# IO-module-8x_fused_in-wall_35x25.net
KiCad netlist of a schematic drawn in EAGLE
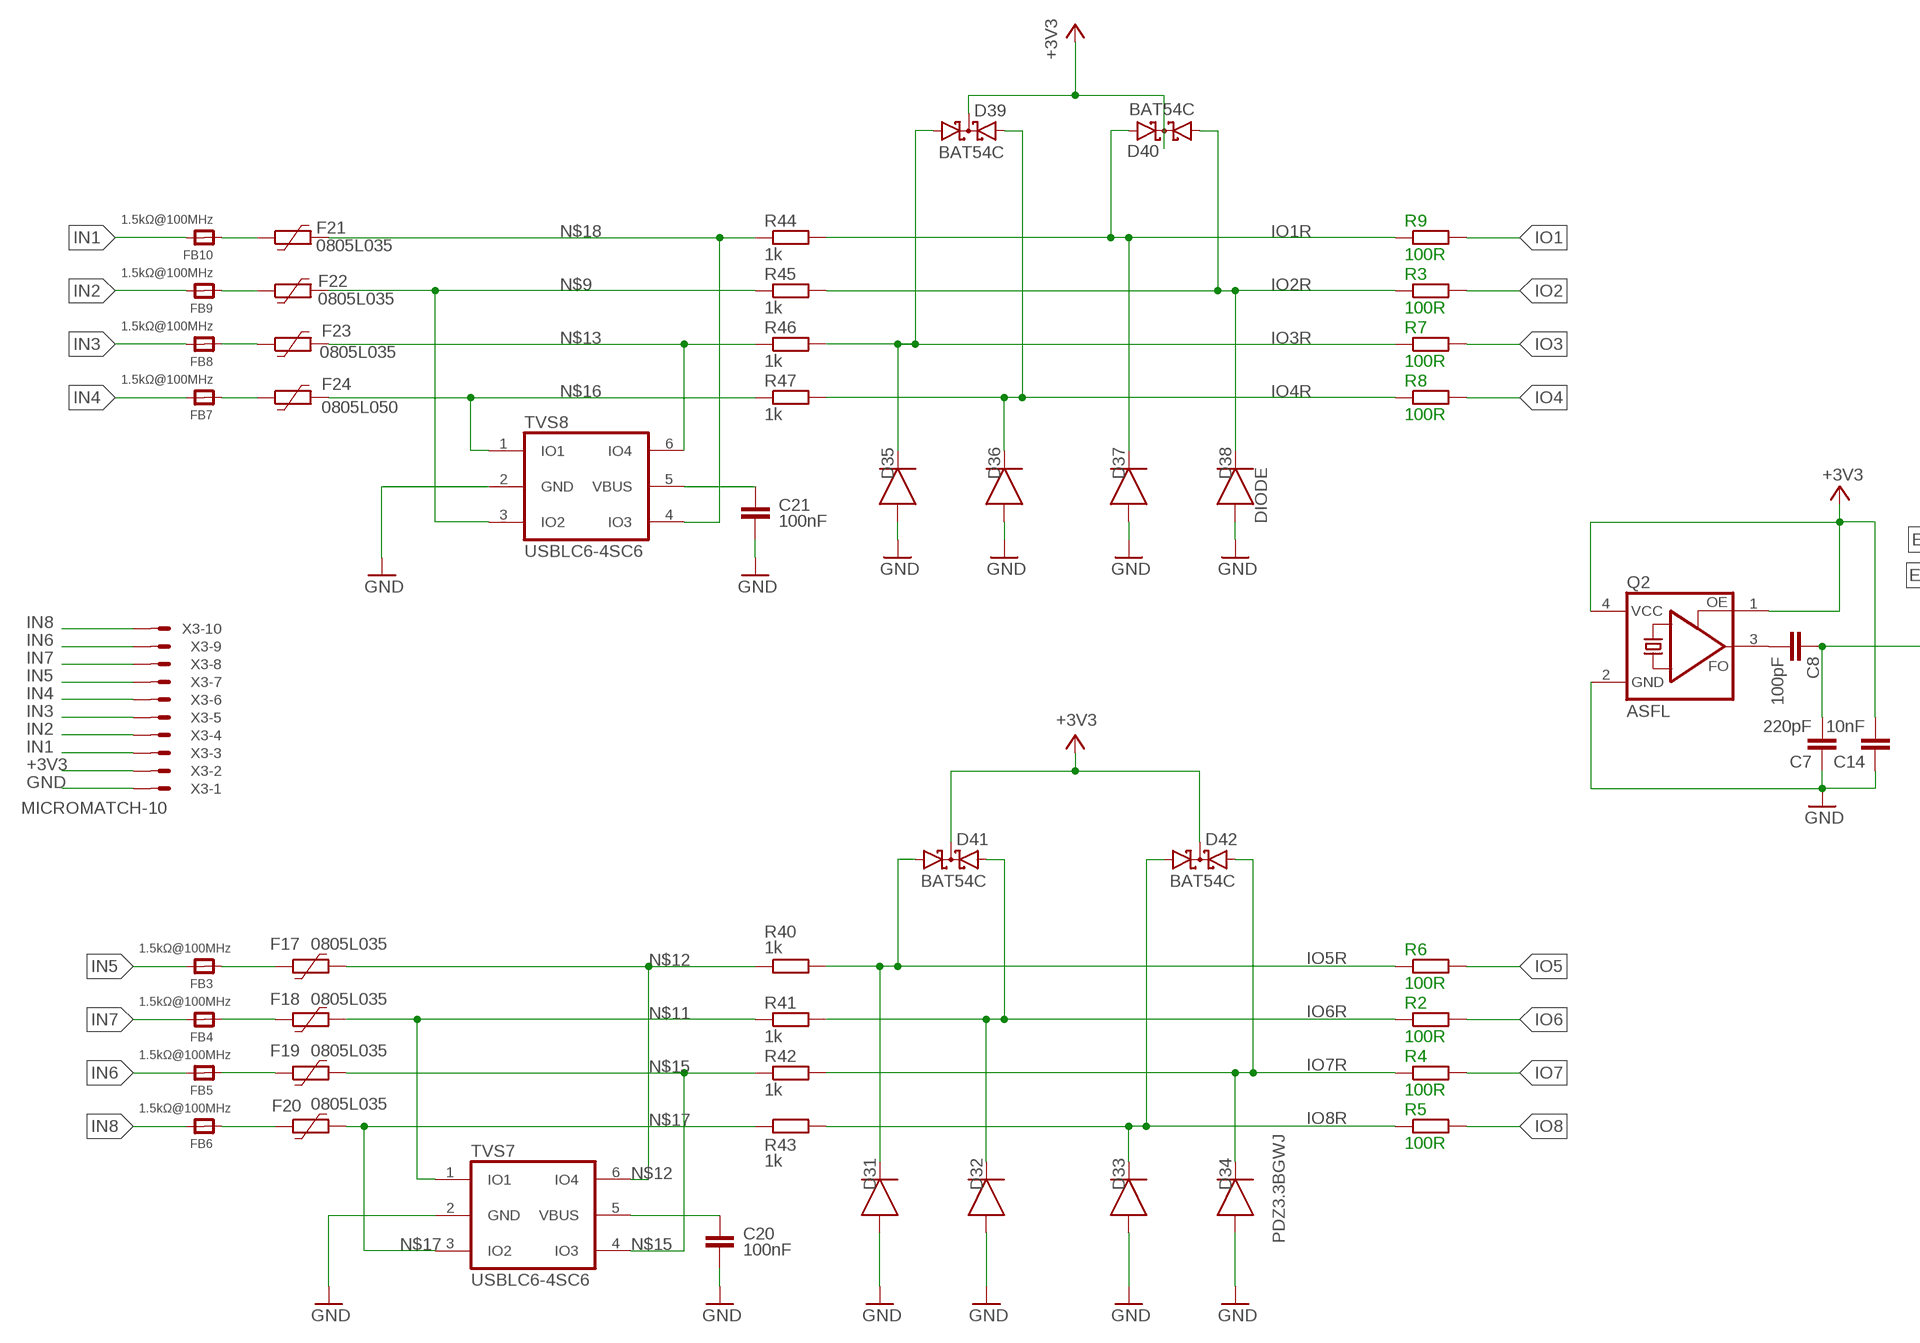
[diagram p0: schematic, sheet 1, part 1 of 2]
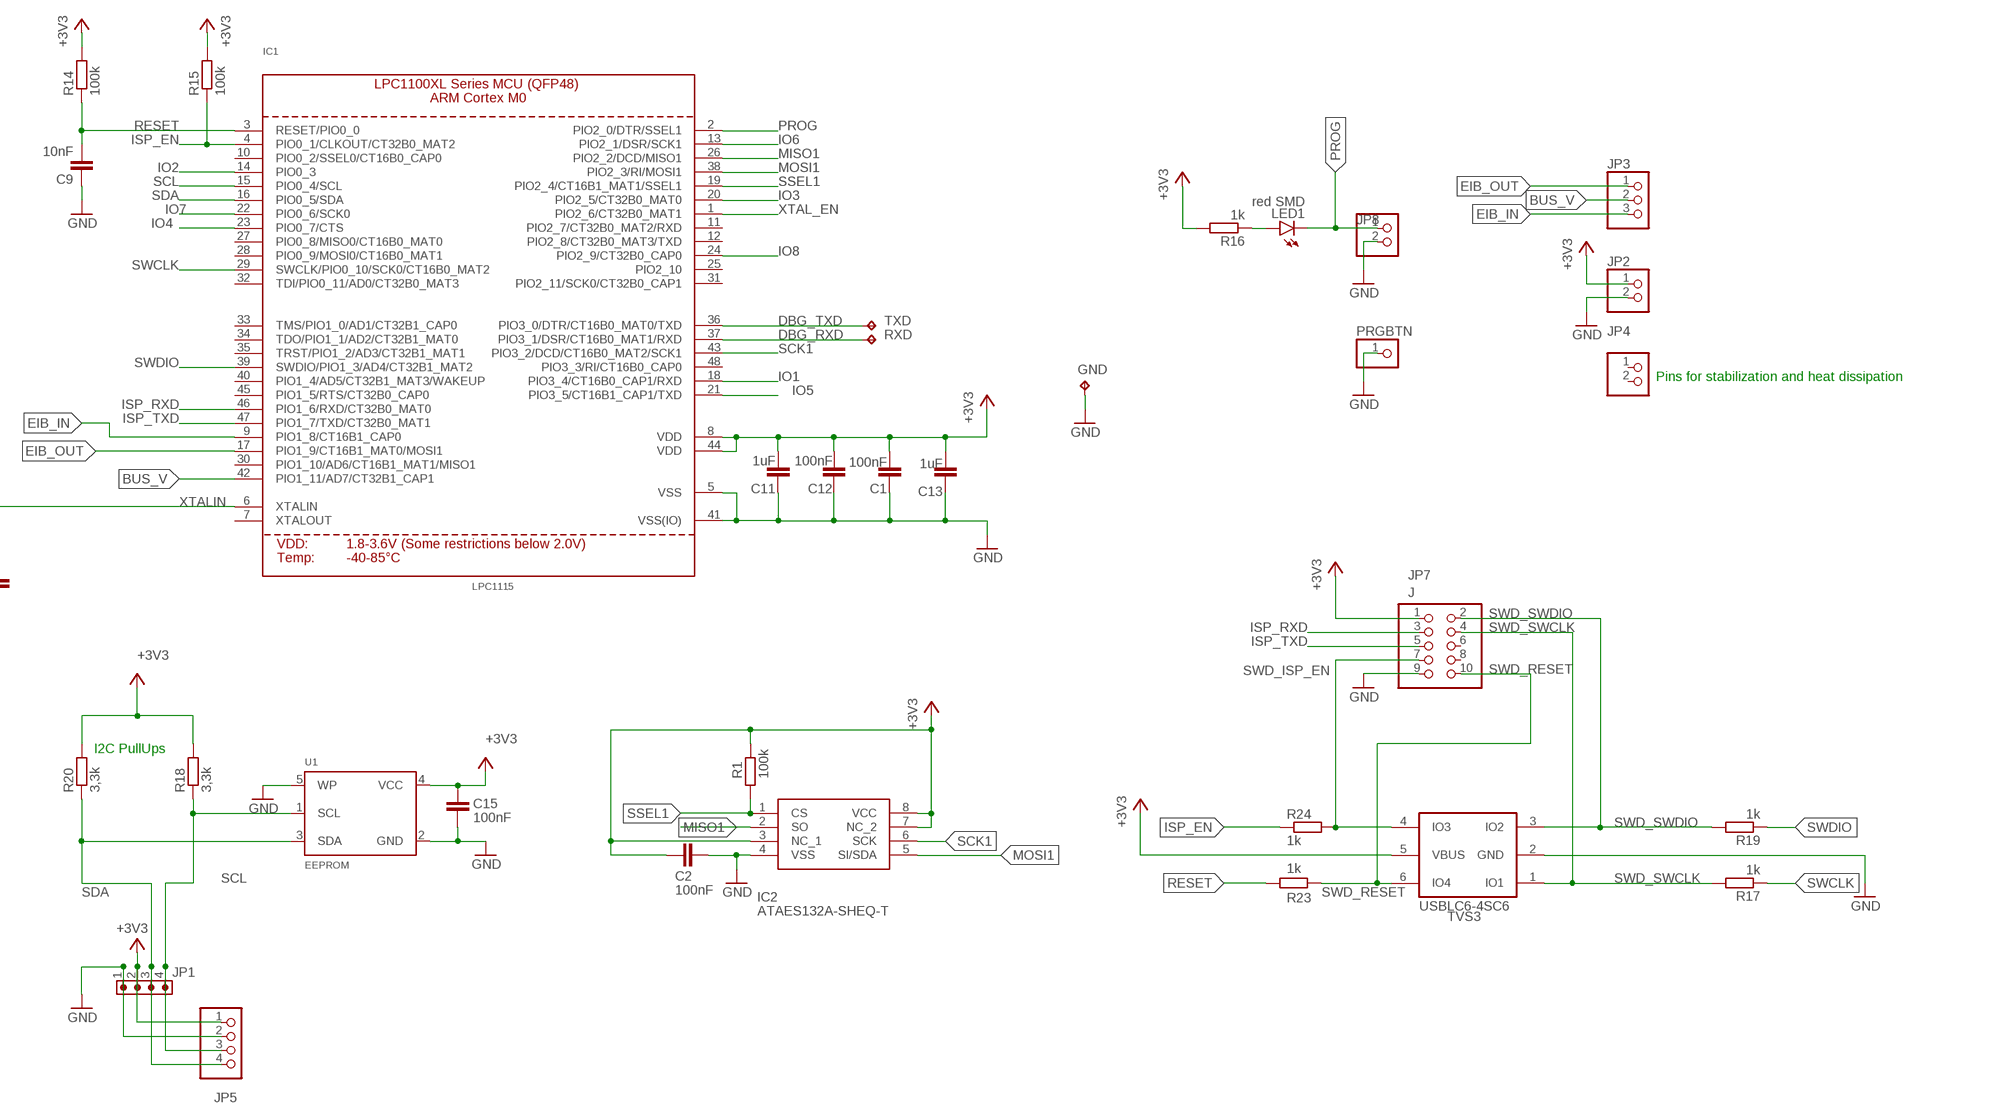
[diagram p1: schematic, sheet 1, part 2 of 2]

(export (version "E")
  (design (tool "Eeschema 10.0.6"))
  (components
    (comp (ref "C1")
      (value "100nF")
      (footprint "eagle-import:C0805")
      (libsource (lib "eagle-import") (part "C-EUC0805"))
    )
    (comp (ref "C2")
      (value "100nF")
      (footprint "eagle-import:C0805")
      (libsource (lib "eagle-import") (part "C-EUC0805"))
    )
    (comp (ref "C7")
      (value "220pF")
      (footprint "eagle-import:C0805")
      (libsource (lib "eagle-import") (part "C-EUC0805"))
    )
    (comp (ref "C8")
      (value "100pF")
      (footprint "eagle-import:C0805")
      (libsource (lib "eagle-import") (part "C-EUC0805"))
    )
    (comp (ref "C9")
      (value "10nF")
      (footprint "eagle-import:C0805")
      (libsource (lib "eagle-import") (part "C-EUC0805"))
    )
    (comp (ref "C11")
      (value "1uF")
      (footprint "eagle-import:C0805")
      (libsource (lib "eagle-import") (part "C-EUC0805"))
    )
    (comp (ref "C12")
      (value "100nF")
      (footprint "eagle-import:C0805")
      (libsource (lib "eagle-import") (part "C-EUC0805"))
    )
    (comp (ref "C13")
      (value "1uF")
      (footprint "eagle-import:C0805")
      (libsource (lib "eagle-import") (part "C-EUC0805"))
    )
    (comp (ref "C14")
      (value "10nF")
      (footprint "eagle-import:C0805")
      (libsource (lib "eagle-import") (part "C-EUC0805"))
    )
    (comp (ref "C15")
      (value "100nF")
      (footprint "eagle-import:C0805")
      (libsource (lib "eagle-import") (part "C-EUC0805"))
    )
    (comp (ref "C20")
      (value "100nF")
      (footprint "eagle-import:C0805")
      (libsource (lib "eagle-import") (part "C-EUC0805"))
    )
    (comp (ref "C21")
      (value "100nF")
      (footprint "eagle-import:C0805")
      (libsource (lib "eagle-import") (part "C-EUC0805"))
    )
    (comp (ref "D31")
      (value "DDZ9684")
      (footprint "eagle-import:SODFL3718X115")
      (libsource (lib "eagle-import") (part "DIODEDO-219-AB(SOD123F)_"))
    )
    (comp (ref "D32")
      (value "DIODE")
      (footprint "eagle-import:SODFL3718X115")
      (libsource (lib "eagle-import") (part "DIODEDO-219-AB(SOD123F)_"))
    )
    (comp (ref "D33")
      (value "DIODE")
      (footprint "eagle-import:SODFL3718X115")
      (libsource (lib "eagle-import") (part "DIODEDO-219-AB(SOD123F)_"))
    )
    (comp (ref "D34")
      (value "PDZ3.3BGWJ")
      (footprint "eagle-import:SODFL3718X115")
      (libsource (lib "eagle-import") (part "DIODEDO-219-AB(SOD123F)_"))
    )
    (comp (ref "D35")
      (value "DIODE")
      (footprint "eagle-import:SODFL3718X115")
      (libsource (lib "eagle-import") (part "DIODEDO-219-AB(SOD123F)_"))
    )
    (comp (ref "D36")
      (value "DIODE")
      (footprint "eagle-import:SODFL3718X115")
      (libsource (lib "eagle-import") (part "DIODEDO-219-AB(SOD123F)_"))
    )
    (comp (ref "D37")
      (value "DIODE")
      (footprint "eagle-import:SODFL3718X115")
      (libsource (lib "eagle-import") (part "DIODEDO-219-AB(SOD123F)_"))
    )
    (comp (ref "D38")
      (value "DIODE")
      (footprint "eagle-import:SODFL3718X115")
      (libsource (lib "eagle-import") (part "DIODEDO-219-AB(SOD123F)_"))
    )
    (comp (ref "D39")
      (value "BAT54C")
      (footprint "eagle-import:SOT23")
      (libsource (lib "eagle-import") (part "BAT54C"))
    )
    (comp (ref "D40")
      (value "BAT54C")
      (footprint "eagle-import:SOT23")
      (libsource (lib "eagle-import") (part "BAT54C"))
    )
    (comp (ref "D41")
      (value "BAT54C")
      (footprint "eagle-import:SOT23")
      (libsource (lib "eagle-import") (part "BAT54C"))
    )
    (comp (ref "D42")
      (value "BAT54C")
      (footprint "eagle-import:SOT23")
      (libsource (lib "eagle-import") (part "BAT54C"))
    )
    (comp (ref "F17")
      (value "0805L035")
      (footprint "eagle-import:0805L")
      (fields (field (name "MF") "Littelfuse"))
      (libsource (lib "eagle-import") (part "?0805L035"))
    )
    (comp (ref "F18")
      (value "0805L035")
      (footprint "eagle-import:0805L")
      (fields (field (name "MF") "Littelfuse"))
      (libsource (lib "eagle-import") (part "?0805L035"))
    )
    (comp (ref "F19")
      (value "0805L035")
      (footprint "eagle-import:0805L")
      (fields (field (name "MF") "Littelfuse"))
      (libsource (lib "eagle-import") (part "?0805L035"))
    )
    (comp (ref "F20")
      (value "0805L035")
      (footprint "eagle-import:0805L")
      (fields (field (name "MF") "Littelfuse"))
      (libsource (lib "eagle-import") (part "?0805L035"))
    )
    (comp (ref "F21")
      (value "0805L035")
      (footprint "eagle-import:0805L")
      (fields (field (name "MF") "Littelfuse"))
      (libsource (lib "eagle-import") (part "?0805L035"))
    )
    (comp (ref "F22")
      (value "0805L035")
      (footprint "eagle-import:0805L")
      (fields (field (name "MF") "Littelfuse"))
      (libsource (lib "eagle-import") (part "?0805L035"))
    )
    (comp (ref "F23")
      (value "0805L035")
      (footprint "eagle-import:0805L")
      (fields (field (name "MF") "Littelfuse"))
      (libsource (lib "eagle-import") (part "?0805L035"))
    )
    (comp (ref "F24")
      (value "0805L050")
      (footprint "eagle-import:0805L")
      (fields (field (name "MF") "Littelfuse"))
      (libsource (lib "eagle-import") (part "?0805L050"))
    )
    (comp (ref "FB3")
      (value "1.5kΩ@100MHz")
      (footprint "eagle-import:0805")
      (libsource (lib "eagle-import") (part "FERRITE0805"))
    )
    (comp (ref "FB4")
      (value "1.5kΩ@100MHz")
      (footprint "eagle-import:0805")
      (libsource (lib "eagle-import") (part "FERRITE0805"))
    )
    (comp (ref "FB5")
      (value "1.5kΩ@100MHz")
      (footprint "eagle-import:0805")
      (libsource (lib "eagle-import") (part "FERRITE0805"))
    )
    (comp (ref "FB6")
      (value "1.5kΩ@100MHz")
      (footprint "eagle-import:0805")
      (libsource (lib "eagle-import") (part "FERRITE0805"))
    )
    (comp (ref "FB7")
      (value "1.5kΩ@100MHz")
      (footprint "eagle-import:0805")
      (libsource (lib "eagle-import") (part "FERRITE0805"))
    )
    (comp (ref "FB8")
      (value "1.5kΩ@100MHz")
      (footprint "eagle-import:0805")
      (libsource (lib "eagle-import") (part "FERRITE0805"))
    )
    (comp (ref "FB9")
      (value "1.5kΩ@100MHz")
      (footprint "eagle-import:0805")
      (libsource (lib "eagle-import") (part "FERRITE0805"))
    )
    (comp (ref "FB10")
      (value "1.5kΩ@100MHz")
      (footprint "eagle-import:0805")
      (libsource (lib "eagle-import") (part "FERRITE0805"))
    )
    (comp (ref "GND")
      (value "TPTP11SQ")
      (footprint "eagle-import:TP11SQ")
      (libsource (lib "eagle-import") (part "TPTP11SQ"))
    )
    (comp (ref "IC1")
      (value "LPC1115")
      (footprint "eagle-import:LQFP48")
      (libsource (lib "eagle-import") (part "LPC1113/4/5_QFP48_XLSERIES"))
    )
    (comp (ref "IC2")
      (value "ATAES132A-SHEQ-T")
      (footprint "eagle-import:SOIC127P600X175-8N")
      (fields (field (name "MOUSER_PART_NUMBER") "556-ATAES132A-SHEQ-T"))
      (libsource (lib "eagle-import") (part "ATAES132A-SHEQ-T"))
    )
    (comp (ref "JP1")
      (value "62000411622")
      (footprint "eagle-import:62000411622")
      (libsource (lib "eagle-import") (part "62000411622"))
    )
    (comp (ref "JP2")
      (value "PINHD-1X2")
      (footprint "eagle-import:1X02")
      (libsource (lib "eagle-import") (part "PINHD-1X2"))
    )
    (comp (ref "JP3")
      (value "PINHD-1X3")
      (footprint "eagle-import:1X03")
      (libsource (lib "eagle-import") (part "PINHD-1X3"))
    )
    (comp (ref "JP4")
      (value "PINHD-1X2")
      (footprint "eagle-import:1X02")
      (libsource (lib "eagle-import") (part "PINHD-1X2"))
    )
    (comp (ref "JP5")
      (value "PINHD-1X4")
      (footprint "eagle-import:1X04")
      (libsource (lib "eagle-import") (part "PINHD-1X4"))
    )
    (comp (ref "JP7")
      (value "J")
      (footprint "eagle-import:2X05M")
      (libsource (lib "eagle-import") (part "PINHD-2X05_2.00"))
    )
    (comp (ref "JP8")
      (value "PINHD-1X2")
      (footprint "eagle-import:1X02")
      (libsource (lib "eagle-import") (part "PINHD-1X2"))
    )
    (comp (ref "LED1")
      (value "red SMD")
      (footprint "eagle-import:CHIPLED_1206")
      (libsource (lib "eagle-import") (part "LEDCHIPLED_1206"))
    )
    (comp (ref "PRGBTN")
      (value "PINHD-1X1")
      (footprint "eagle-import:1X01")
      (libsource (lib "eagle-import") (part "PINHD-1X1"))
    )
    (comp (ref "Q2")
      (value "ASFL")
      (footprint "eagle-import:ASF")
      (fields (field (name "MPN") "ASFLM1-50.000MHZ-C-T"))
      (libsource (lib "eagle-import") (part "ASFL"))
    )
    (comp (ref "R1")
      (value "100k")
      (footprint "eagle-import:R0805")
      (libsource (lib "eagle-import") (part "R-EU_R0805"))
    )
    (comp (ref "R2")
      (value "100R")
      (footprint "eagle-import:R0805")
      (libsource (lib "eagle-import") (part "R-EU_R0805"))
    )
    (comp (ref "R3")
      (value "100R")
      (footprint "eagle-import:R0805")
      (libsource (lib "eagle-import") (part "R-EU_R0805"))
    )
    (comp (ref "R4")
      (value "100R")
      (footprint "eagle-import:R0805")
      (libsource (lib "eagle-import") (part "R-EU_R0805"))
    )
    (comp (ref "R5")
      (value "100R")
      (footprint "eagle-import:R0805")
      (libsource (lib "eagle-import") (part "R-EU_R0805"))
    )
    (comp (ref "R6")
      (value "100R")
      (footprint "eagle-import:R0805")
      (libsource (lib "eagle-import") (part "R-EU_R0805"))
    )
    (comp (ref "R7")
      (value "100R")
      (footprint "eagle-import:R0805")
      (libsource (lib "eagle-import") (part "R-EU_R0805"))
    )
    (comp (ref "R8")
      (value "100R")
      (footprint "eagle-import:R0805")
      (libsource (lib "eagle-import") (part "R-EU_R0805"))
    )
    (comp (ref "R9")
      (value "100R")
      (footprint "eagle-import:R0805")
      (libsource (lib "eagle-import") (part "R-EU_R0805"))
    )
    (comp (ref "R14")
      (value "100k")
      (footprint "eagle-import:R0805")
      (libsource (lib "eagle-import") (part "R-EU_R0805"))
    )
    (comp (ref "R15")
      (value "100k")
      (footprint "eagle-import:R0805")
      (libsource (lib "eagle-import") (part "R-EU_R0805"))
    )
    (comp (ref "R16")
      (value "1k")
      (footprint "eagle-import:R0805")
      (libsource (lib "eagle-import") (part "R-EU_R0805"))
    )
    (comp (ref "R17")
      (value "1k")
      (footprint "eagle-import:R0805")
      (libsource (lib "eagle-import") (part "R-EU_R0805"))
    )
    (comp (ref "R18")
      (value "3,3k")
      (footprint "eagle-import:R0805")
      (libsource (lib "eagle-import") (part "R-EU_R0805"))
    )
    (comp (ref "R19")
      (value "1k")
      (footprint "eagle-import:R0805")
      (libsource (lib "eagle-import") (part "R-EU_R0805"))
    )
    (comp (ref "R20")
      (value "3,3k")
      (footprint "eagle-import:R0805")
      (libsource (lib "eagle-import") (part "R-EU_R0805"))
    )
    (comp (ref "R23")
      (value "1k")
      (footprint "eagle-import:R0805")
      (libsource (lib "eagle-import") (part "R-EU_R0805"))
    )
    (comp (ref "R24")
      (value "1k")
      (footprint "eagle-import:R0805")
      (libsource (lib "eagle-import") (part "R-EU_R0805"))
    )
    (comp (ref "R40")
      (value "1k")
      (footprint "eagle-import:R0805")
      (libsource (lib "eagle-import") (part "R-EU_R0805"))
    )
    (comp (ref "R41")
      (value "1k")
      (footprint "eagle-import:R0805")
      (libsource (lib "eagle-import") (part "R-EU_R0805"))
    )
    (comp (ref "R42")
      (value "1k")
      (footprint "eagle-import:R0805")
      (libsource (lib "eagle-import") (part "R-EU_R0805"))
    )
    (comp (ref "R43")
      (value "1k")
      (footprint "eagle-import:R0805")
      (libsource (lib "eagle-import") (part "R-EU_R0805"))
    )
    (comp (ref "R44")
      (value "1k")
      (footprint "eagle-import:R0805")
      (libsource (lib "eagle-import") (part "R-EU_R0805"))
    )
    (comp (ref "R45")
      (value "1k")
      (footprint "eagle-import:R0805")
      (libsource (lib "eagle-import") (part "R-EU_R0805"))
    )
    (comp (ref "R46")
      (value "1k")
      (footprint "eagle-import:R0805")
      (libsource (lib "eagle-import") (part "R-EU_R0805"))
    )
    (comp (ref "R47")
      (value "1k")
      (footprint "eagle-import:R0805")
      (libsource (lib "eagle-import") (part "R-EU_R0805"))
    )
    (comp (ref "RXD")
      (value "TPTP12R")
      (footprint "eagle-import:TP12R")
      (libsource (lib "eagle-import") (part "TPTP12R"))
    )
    (comp (ref "TVS3")
      (value "USBLC6-4SC6")
      (footprint "eagle-import:SOT-23-6L")
      (libsource (lib "eagle-import") (part "USBLC6-4SC6"))
    )
    (comp (ref "TVS7")
      (value "USBLC6-4SC6")
      (footprint "eagle-import:SOT-23-6L")
      (libsource (lib "eagle-import") (part "USBLC6-4SC6"))
    )
    (comp (ref "TVS8")
      (value "USBLC6-4SC6")
      (footprint "eagle-import:SOT-23-6L")
      (libsource (lib "eagle-import") (part "USBLC6-4SC6"))
    )
    (comp (ref "TXD")
      (value "TPTP12SQ")
      (footprint "eagle-import:TP12SQ")
      (libsource (lib "eagle-import") (part "TPTP12SQ"))
    )
    (comp (ref "U1")
      (value "EEPROM")
      (footprint "eagle-import:SOT23-5")
      (libsource (lib "eagle-import") (part "EEPROM_I2C_MCP24AA32"))
    )
    (comp (ref "X3")
      (value "MICROMATCH-10")
      (footprint "eagle-import:MICROMATCH-10")
      (fields (field (name "MF") "FARNELL") (field (name "MPN") "8-215464-0"))
      (libsource (lib "eagle-import") (part "MICROMATCH-10"))
    )
  )
  (nets
    (net (code "1") (name "+3V3") (class "Default")
      (node (ref "C1") (pin "2") (pinfunction "2_2") (pintype "passive"))
      (node (ref "C11") (pin "2") (pinfunction "2_2") (pintype "passive"))
      (node (ref "C12") (pin "2") (pinfunction "2_2") (pintype "passive"))
      (node (ref "C13") (pin "2") (pinfunction "2_2") (pintype "passive"))
      (node (ref "C14") (pin "2") (pinfunction "2_2") (pintype "passive"))
      (node (ref "C15") (pin "1") (pinfunction "1_1") (pintype "passive"))
      (node (ref "C2") (pin "1") (pinfunction "1_1") (pintype "passive"))
      (node (ref "D39") (pin "3") (pinfunction "CC_3") (pintype "passive"))
      (node (ref "D40") (pin "3") (pinfunction "CC_3") (pintype "passive"))
      (node (ref "D41") (pin "3") (pinfunction "CC_3") (pintype "passive"))
      (node (ref "D42") (pin "3") (pinfunction "CC_3") (pintype "passive"))
      (node (ref "IC1") (pin "44") (pinfunction "VDD_44") (pintype "power_in"))
      (node (ref "IC1") (pin "8") (pinfunction "VDD_8") (pintype "power_in"))
      (node (ref "IC2") (pin "3") (pinfunction "NC_1_3") (pintype "bidirectional"))
      (node (ref "IC2") (pin "7") (pinfunction "NC_2_7") (pintype "bidirectional"))
      (node (ref "IC2") (pin "8") (pinfunction "VCC_8") (pintype "bidirectional"))
      (node (ref "JP1") (pin "2") (pinfunction "2_2") (pintype "passive"))
      (node (ref "JP2") (pin "1") (pinfunction "1_1") (pintype "passive"))
      (node (ref "JP5") (pin "1") (pinfunction "1_1") (pintype "passive"))
      (node (ref "JP7") (pin "1") (pinfunction "1_1") (pintype "passive"))
      (node (ref "Q2") (pin "1") (pinfunction "OE_1") (pintype "input"))
      (node (ref "Q2") (pin "4") (pinfunction "VCC_4") (pintype "power_in"))
      (node (ref "R1") (pin "2") (pinfunction "2_2") (pintype "passive"))
      (node (ref "R14") (pin "2") (pinfunction "2_2") (pintype "passive"))
      (node (ref "R15") (pin "2") (pinfunction "2_2") (pintype "passive"))
      (node (ref "R16") (pin "2") (pinfunction "2_2") (pintype "passive"))
      (node (ref "R18") (pin "2") (pinfunction "2_2") (pintype "passive"))
      (node (ref "R20") (pin "2") (pinfunction "2_2") (pintype "passive"))
      (node (ref "TVS3") (pin "5") (pinfunction "VBUS_5") (pintype "bidirectional"))
      (node (ref "U1") (pin "4") (pinfunction "VCC_4") (pintype "bidirectional"))
      (node (ref "X3") (pin "2") (pinfunction "S_2") (pintype "passive"))
    )
    (net (code "2") (name "/DBG_RXD") (class "Default")
      (node (ref "IC1") (pin "37") (pinfunction "PIO3_1/DSR/CT16B0_MAT1/RXD_37") (pintype "bidirectional"))
      (node (ref "RXD") (pin "TP") (pinfunction "TP_TP") (pintype "input"))
    )
    (net (code "3") (name "/DBG_TXD") (class "Default")
      (node (ref "IC1") (pin "36") (pinfunction "PIO3_0/DTR/CT16B0_MAT0/TXD_36") (pintype "bidirectional"))
      (node (ref "TXD") (pin "TP") (pinfunction "TP_TP") (pintype "input"))
    )
    (net (code "4") (name "/IO1R") (class "Default")
      (node (ref "D37") (pin "1") (pinfunction "C_1") (pintype "passive"))
      (node (ref "D40") (pin "2") (pinfunction "A2_2") (pintype "passive"))
      (node (ref "R44") (pin "2") (pinfunction "2_2") (pintype "passive"))
      (node (ref "R9") (pin "1") (pinfunction "1_1") (pintype "passive"))
    )
    (net (code "5") (name "/IO2R") (class "Default")
      (node (ref "D38") (pin "1") (pinfunction "C_1") (pintype "passive"))
      (node (ref "D40") (pin "1") (pinfunction "A1_1") (pintype "passive"))
      (node (ref "R3") (pin "1") (pinfunction "1_1") (pintype "passive"))
      (node (ref "R45") (pin "2") (pinfunction "2_2") (pintype "passive"))
    )
    (net (code "6") (name "/IO3R") (class "Default")
      (node (ref "D35") (pin "1") (pinfunction "C_1") (pintype "passive"))
      (node (ref "D39") (pin "1") (pinfunction "A1_1") (pintype "passive"))
      (node (ref "R46") (pin "2") (pinfunction "2_2") (pintype "passive"))
      (node (ref "R7") (pin "1") (pinfunction "1_1") (pintype "passive"))
    )
    (net (code "7") (name "/IO4R") (class "Default")
      (node (ref "D36") (pin "1") (pinfunction "C_1") (pintype "passive"))
      (node (ref "D39") (pin "2") (pinfunction "A2_2") (pintype "passive"))
      (node (ref "R47") (pin "2") (pinfunction "2_2") (pintype "passive"))
      (node (ref "R8") (pin "1") (pinfunction "1_1") (pintype "passive"))
    )
    (net (code "8") (name "/IO5R") (class "Default")
      (node (ref "D31") (pin "1") (pinfunction "C_1") (pintype "passive"))
      (node (ref "D41") (pin "1") (pinfunction "A1_1") (pintype "passive"))
      (node (ref "R40") (pin "2") (pinfunction "2_2") (pintype "passive"))
      (node (ref "R6") (pin "1") (pinfunction "1_1") (pintype "passive"))
    )
    (net (code "9") (name "/IO6R") (class "Default")
      (node (ref "D32") (pin "1") (pinfunction "C_1") (pintype "passive"))
      (node (ref "D41") (pin "2") (pinfunction "A2_2") (pintype "passive"))
      (node (ref "R2") (pin "1") (pinfunction "1_1") (pintype "passive"))
      (node (ref "R41") (pin "2") (pinfunction "2_2") (pintype "passive"))
    )
    (net (code "10") (name "/IO7R") (class "Default")
      (node (ref "D34") (pin "1") (pinfunction "C_1") (pintype "passive"))
      (node (ref "D42") (pin "2") (pinfunction "A2_2") (pintype "passive"))
      (node (ref "R4") (pin "1") (pinfunction "1_1") (pintype "passive"))
      (node (ref "R42") (pin "2") (pinfunction "2_2") (pintype "passive"))
    )
    (net (code "11") (name "/IO8R") (class "Default")
      (node (ref "D33") (pin "1") (pinfunction "C_1") (pintype "passive"))
      (node (ref "D42") (pin "1") (pinfunction "A1_1") (pintype "passive"))
      (node (ref "R43") (pin "2") (pinfunction "2_2") (pintype "passive"))
      (node (ref "R5") (pin "1") (pinfunction "1_1") (pintype "passive"))
    )
    (net (code "12") (name "/ISP_RXD") (class "Default")
      (node (ref "IC1") (pin "46") (pinfunction "PIO1_6/RXD/CT32B0_MAT0_46") (pintype "bidirectional"))
      (node (ref "JP7") (pin "3") (pinfunction "3_3") (pintype "passive"))
    )
    (net (code "13") (name "/ISP_TXD") (class "Default")
      (node (ref "IC1") (pin "47") (pinfunction "PIO1_7/TXD/CT32B0_MAT1_47") (pintype "bidirectional"))
      (node (ref "JP7") (pin "5") (pinfunction "5_5") (pintype "passive"))
    )
    (net (code "14") (name "/N$9") (class "Default")
      (node (ref "F22") (pin "2") (pinfunction "2_2") (pintype "passive"))
      (node (ref "R45") (pin "1") (pinfunction "1_1") (pintype "passive"))
      (node (ref "TVS8") (pin "3") (pinfunction "IO2_3") (pintype "bidirectional"))
    )
    (net (code "15") (name "/N$11") (class "Default")
      (node (ref "F18") (pin "2") (pinfunction "2_2") (pintype "passive"))
      (node (ref "R41") (pin "1") (pinfunction "1_1") (pintype "passive"))
      (node (ref "TVS7") (pin "1") (pinfunction "IO1_1") (pintype "bidirectional"))
    )
    (net (code "16") (name "/N$12") (class "Default")
      (node (ref "F17") (pin "2") (pinfunction "2_2") (pintype "passive"))
      (node (ref "R40") (pin "1") (pinfunction "1_1") (pintype "passive"))
      (node (ref "TVS7") (pin "6") (pinfunction "IO4_6") (pintype "bidirectional"))
    )
    (net (code "17") (name "/N$13") (class "Default")
      (node (ref "F23") (pin "2") (pinfunction "2_2") (pintype "passive"))
      (node (ref "R46") (pin "1") (pinfunction "1_1") (pintype "passive"))
      (node (ref "TVS8") (pin "6") (pinfunction "IO4_6") (pintype "bidirectional"))
    )
    (net (code "18") (name "/N$15") (class "Default")
      (node (ref "F19") (pin "2") (pinfunction "2_2") (pintype "passive"))
      (node (ref "R42") (pin "1") (pinfunction "1_1") (pintype "passive"))
      (node (ref "TVS7") (pin "4") (pinfunction "IO3_4") (pintype "bidirectional"))
    )
    (net (code "19") (name "/N$16") (class "Default")
      (node (ref "F24") (pin "2") (pinfunction "2_2") (pintype "passive"))
      (node (ref "R47") (pin "1") (pinfunction "1_1") (pintype "passive"))
      (node (ref "TVS8") (pin "1") (pinfunction "IO1_1") (pintype "bidirectional"))
    )
    (net (code "20") (name "/N$17") (class "Default")
      (node (ref "F20") (pin "2") (pinfunction "2_2") (pintype "passive"))
      (node (ref "R43") (pin "1") (pinfunction "1_1") (pintype "passive"))
      (node (ref "TVS7") (pin "3") (pinfunction "IO2_3") (pintype "bidirectional"))
    )
    (net (code "21") (name "/N$18") (class "Default")
      (node (ref "F21") (pin "2") (pinfunction "2_2") (pintype "passive"))
      (node (ref "R44") (pin "1") (pinfunction "1_1") (pintype "passive"))
      (node (ref "TVS8") (pin "4") (pinfunction "IO3_4") (pintype "bidirectional"))
    )
    (net (code "22") (name "/SCL") (class "Default")
      (node (ref "IC1") (pin "15") (pinfunction "PIO0_4/SCL_15") (pintype "bidirectional"))
      (node (ref "JP1") (pin "4") (pinfunction "4_4") (pintype "passive"))
      (node (ref "JP5") (pin "3") (pinfunction "3_3") (pintype "passive"))
      (node (ref "R18") (pin "1") (pinfunction "1_1") (pintype "passive"))
      (node (ref "U1") (pin "1") (pinfunction "SCL_1") (pintype "bidirectional"))
    )
    (net (code "23") (name "/SDA") (class "Default")
      (node (ref "IC1") (pin "16") (pinfunction "PIO0_5/SDA_16") (pintype "bidirectional"))
      (node (ref "JP1") (pin "3") (pinfunction "3_3") (pintype "passive"))
      (node (ref "JP5") (pin "4") (pinfunction "4_4") (pintype "passive"))
      (node (ref "R20") (pin "1") (pinfunction "1_1") (pintype "passive"))
      (node (ref "U1") (pin "3") (pinfunction "SDA_3") (pintype "bidirectional"))
    )
    (net (code "24") (name "/SWD_ISP_EN") (class "Default")
      (node (ref "JP7") (pin "7") (pinfunction "7_7") (pintype "passive"))
      (node (ref "R24") (pin "2") (pinfunction "2_2") (pintype "passive"))
      (node (ref "TVS3") (pin "4") (pinfunction "IO3_4") (pintype "bidirectional"))
    )
    (net (code "25") (name "/SWD_RESET") (class "Default")
      (node (ref "JP7") (pin "10") (pinfunction "10_10") (pintype "passive"))
      (node (ref "R23") (pin "1") (pinfunction "1_1") (pintype "passive"))
      (node (ref "TVS3") (pin "6") (pinfunction "IO4_6") (pintype "bidirectional"))
    )
    (net (code "26") (name "/SWD_SWCLK") (class "Default")
      (node (ref "JP7") (pin "4") (pinfunction "4_4") (pintype "passive"))
      (node (ref "R17") (pin "2") (pinfunction "2_2") (pintype "passive"))
      (node (ref "TVS3") (pin "1") (pinfunction "IO1_1") (pintype "bidirectional"))
    )
    (net (code "27") (name "/SWD_SWDIO") (class "Default")
      (node (ref "JP7") (pin "2") (pinfunction "2_2") (pintype "passive"))
      (node (ref "R19") (pin "2") (pinfunction "2_2") (pintype "passive"))
      (node (ref "TVS3") (pin "3") (pinfunction "IO2_3") (pintype "bidirectional"))
    )
    (net (code "28") (name "/XTALIN") (class "Default")
      (node (ref "C7") (pin "2") (pinfunction "2_2") (pintype "passive"))
      (node (ref "C8") (pin "1") (pinfunction "1_1") (pintype "passive"))
      (node (ref "IC1") (pin "6") (pinfunction "XTALIN_6") (pintype "input"))
    )
    (net (code "29") (name "/XTAL_EN") (class "Default")
      (node (ref "IC1") (pin "1") (pinfunction "PIO2_6/CT32B0_MAT1_1") (pintype "bidirectional"))
    )
    (net (code "30") (name "BUS_V") (class "Default")
      (node (ref "IC1") (pin "42") (pinfunction "PIO1_11/AD7/CT32B1_CAP1_42") (pintype "bidirectional"))
      (node (ref "JP3") (pin "2") (pinfunction "2_2") (pintype "passive"))
    )
    (net (code "31") (name "EIB_IN") (class "Default")
      (node (ref "IC1") (pin "9") (pinfunction "PIO1_8/CT16B1_CAP0_9") (pintype "bidirectional"))
      (node (ref "JP3") (pin "3") (pinfunction "3_3") (pintype "passive"))
    )
    (net (code "32") (name "EIB_OUT") (class "Default")
      (node (ref "IC1") (pin "17") (pinfunction "PIO1_9/CT16B1_MAT0/MOSI1_17") (pintype "bidirectional"))
      (node (ref "JP3") (pin "1") (pinfunction "1_1") (pintype "passive"))
    )
    (net (code "33") (name "GND") (class "Default")
      (node (ref "C1") (pin "1") (pinfunction "1_1") (pintype "passive"))
      (node (ref "C11") (pin "1") (pinfunction "1_1") (pintype "passive"))
      (node (ref "C12") (pin "1") (pinfunction "1_1") (pintype "passive"))
      (node (ref "C13") (pin "1") (pinfunction "1_1") (pintype "passive"))
      (node (ref "C14") (pin "1") (pinfunction "1_1") (pintype "passive"))
      (node (ref "C15") (pin "2") (pinfunction "2_2") (pintype "passive"))
      (node (ref "C2") (pin "2") (pinfunction "2_2") (pintype "passive"))
      (node (ref "C20") (pin "1") (pinfunction "1_1") (pintype "passive"))
      (node (ref "C21") (pin "1") (pinfunction "1_1") (pintype "passive"))
      (node (ref "C7") (pin "1") (pinfunction "1_1") (pintype "passive"))
      (node (ref "C9") (pin "1") (pinfunction "1_1") (pintype "passive"))
      (node (ref "D31") (pin "2") (pinfunction "A_2") (pintype "passive"))
      (node (ref "D32") (pin "2") (pinfunction "A_2") (pintype "passive"))
      (node (ref "D33") (pin "2") (pinfunction "A_2") (pintype "passive"))
      (node (ref "D34") (pin "2") (pinfunction "A_2") (pintype "passive"))
      (node (ref "D35") (pin "2") (pinfunction "A_2") (pintype "passive"))
      (node (ref "D36") (pin "2") (pinfunction "A_2") (pintype "passive"))
      (node (ref "D37") (pin "2") (pinfunction "A_2") (pintype "passive"))
      (node (ref "D38") (pin "2") (pinfunction "A_2") (pintype "passive"))
      (node (ref "GND") (pin "TP") (pinfunction "TP_TP") (pintype "input"))
      (node (ref "IC1") (pin "41") (pinfunction "VSS(IO)_41") (pintype "power_in"))
      (node (ref "IC1") (pin "5") (pinfunction "VSS_5") (pintype "power_in"))
      (node (ref "IC2") (pin "4") (pinfunction "VSS_4") (pintype "bidirectional"))
      (node (ref "JP1") (pin "1") (pinfunction "1_1") (pintype "passive"))
      (node (ref "JP2") (pin "2") (pinfunction "2_2") (pintype "passive"))
      (node (ref "JP5") (pin "2") (pinfunction "2_2") (pintype "passive"))
      (node (ref "JP7") (pin "9") (pinfunction "9_9") (pintype "passive"))
      (node (ref "JP8") (pin "2") (pinfunction "2_2") (pintype "passive"))
      (node (ref "PRGBTN") (pin "1") (pinfunction "1_1") (pintype "passive"))
      (node (ref "Q2") (pin "2") (pinfunction "GND_2") (pintype "power_in"))
      (node (ref "TVS3") (pin "2") (pinfunction "GND_2") (pintype "bidirectional"))
      (node (ref "TVS7") (pin "2") (pinfunction "GND_2") (pintype "bidirectional"))
      (node (ref "TVS8") (pin "2") (pinfunction "GND_2") (pintype "bidirectional"))
      (node (ref "U1") (pin "2") (pinfunction "GND_2") (pintype "bidirectional"))
      (node (ref "U1") (pin "5") (pinfunction "WP_5") (pintype "bidirectional"))
      (node (ref "X3") (pin "1") (pinfunction "S_1") (pintype "passive"))
    )
    (net (code "34") (name "IN1") (class "Default")
      (node (ref "FB10") (pin "2") (pinfunction "P$2_2") (pintype "passive"))
      (node (ref "X3") (pin "3") (pinfunction "S_3") (pintype "passive"))
    )
    (net (code "35") (name "IN2") (class "Default")
      (node (ref "FB9") (pin "2") (pinfunction "P$2_2") (pintype "passive"))
      (node (ref "X3") (pin "4") (pinfunction "S_4") (pintype "passive"))
    )
    (net (code "36") (name "IN3") (class "Default")
      (node (ref "FB8") (pin "2") (pinfunction "P$2_2") (pintype "passive"))
      (node (ref "X3") (pin "5") (pinfunction "S_5") (pintype "passive"))
    )
    (net (code "37") (name "IN4") (class "Default")
      (node (ref "FB7") (pin "2") (pinfunction "P$2_2") (pintype "passive"))
      (node (ref "X3") (pin "6") (pinfunction "S_6") (pintype "passive"))
    )
    (net (code "38") (name "IN5") (class "Default")
      (node (ref "FB3") (pin "2") (pinfunction "P$2_2") (pintype "passive"))
      (node (ref "X3") (pin "7") (pinfunction "S_7") (pintype "passive"))
    )
    (net (code "39") (name "IN6") (class "Default")
      (node (ref "FB5") (pin "2") (pinfunction "P$2_2") (pintype "passive"))
      (node (ref "X3") (pin "9") (pinfunction "S_9") (pintype "passive"))
    )
    (net (code "40") (name "IN7") (class "Default")
      (node (ref "FB4") (pin "2") (pinfunction "P$2_2") (pintype "passive"))
      (node (ref "X3") (pin "8") (pinfunction "S_8") (pintype "passive"))
    )
    (net (code "41") (name "IN8") (class "Default")
      (node (ref "FB6") (pin "2") (pinfunction "P$2_2") (pintype "passive"))
      (node (ref "X3") (pin "10") (pinfunction "S_10") (pintype "passive"))
    )
    (net (code "42") (name "IO1") (class "Default")
      (node (ref "IC1") (pin "18") (pinfunction "PIO3_4/CT16B0_CAP1/RXD_18") (pintype "bidirectional"))
      (node (ref "R9") (pin "2") (pinfunction "2_2") (pintype "passive"))
    )
    (net (code "43") (name "IO2") (class "Default")
      (node (ref "IC1") (pin "14") (pinfunction "PIO0_3_14") (pintype "bidirectional"))
      (node (ref "R3") (pin "2") (pinfunction "2_2") (pintype "passive"))
    )
    (net (code "44") (name "IO3") (class "Default")
      (node (ref "IC1") (pin "20") (pinfunction "PIO2_5/CT32B0_MAT0_20") (pintype "bidirectional"))
      (node (ref "R7") (pin "2") (pinfunction "2_2") (pintype "passive"))
    )
    (net (code "45") (name "IO4") (class "Default")
      (node (ref "IC1") (pin "23") (pinfunction "PIO0_7/CTS_23") (pintype "bidirectional"))
      (node (ref "R8") (pin "2") (pinfunction "2_2") (pintype "passive"))
    )
    (net (code "46") (name "IO5") (class "Default")
      (node (ref "IC1") (pin "21") (pinfunction "PIO3_5/CT16B1_CAP1/TXD_21") (pintype "bidirectional"))
      (node (ref "R6") (pin "2") (pinfunction "2_2") (pintype "passive"))
    )
    (net (code "47") (name "IO6") (class "Default")
      (node (ref "IC1") (pin "13") (pinfunction "PIO2_1/DSR/SCK1_13") (pintype "bidirectional"))
      (node (ref "R2") (pin "2") (pinfunction "2_2") (pintype "passive"))
    )
    (net (code "48") (name "IO7") (class "Default")
      (node (ref "IC1") (pin "22") (pinfunction "PIO0_6/SCK0_22") (pintype "bidirectional"))
      (node (ref "R4") (pin "2") (pinfunction "2_2") (pintype "passive"))
    )
    (net (code "49") (name "IO8") (class "Default")
      (node (ref "IC1") (pin "24") (pinfunction "PIO2_9/CT32B0_CAP0_24") (pintype "bidirectional"))
      (node (ref "R5") (pin "2") (pinfunction "2_2") (pintype "passive"))
    )
    (net (code "50") (name "ISP_EN") (class "Default")
      (node (ref "IC1") (pin "4") (pinfunction "PIO0_1/CLKOUT/CT32B0_MAT2_4") (pintype "bidirectional"))
      (node (ref "R15") (pin "1") (pinfunction "1_1") (pintype "passive"))
      (node (ref "R24") (pin "1") (pinfunction "1_1") (pintype "passive"))
    )
    (net (code "51") (name "MISO1") (class "Default")
      (node (ref "IC1") (pin "26") (pinfunction "PIO2_2/DCD/MISO1_26") (pintype "bidirectional"))
      (node (ref "IC2") (pin "2") (pinfunction "SO_2") (pintype "bidirectional"))
    )
    (net (code "52") (name "MOSI1") (class "Default")
      (node (ref "IC1") (pin "38") (pinfunction "PIO2_3/RI/MOSI1_38") (pintype "bidirectional"))
      (node (ref "IC2") (pin "5") (pinfunction "SI/SDA_5") (pintype "bidirectional"))
    )
    (net (code "53") (name "Net-(FB3-P$1)") (class "Default")
      (node (ref "F17") (pin "1") (pinfunction "1_1") (pintype "passive"))
      (node (ref "FB3") (pin "1") (pinfunction "P$1_1") (pintype "passive"))
    )
    (net (code "54") (name "Net-(FB4-P$1)") (class "Default")
      (node (ref "F18") (pin "1") (pinfunction "1_1") (pintype "passive"))
      (node (ref "FB4") (pin "1") (pinfunction "P$1_1") (pintype "passive"))
    )
    (net (code "55") (name "Net-(FB5-P$1)") (class "Default")
      (node (ref "F19") (pin "1") (pinfunction "1_1") (pintype "passive"))
      (node (ref "FB5") (pin "1") (pinfunction "P$1_1") (pintype "passive"))
    )
    (net (code "56") (name "Net-(FB6-P$1)") (class "Default")
      (node (ref "F20") (pin "1") (pinfunction "1_1") (pintype "passive"))
      (node (ref "FB6") (pin "1") (pinfunction "P$1_1") (pintype "passive"))
    )
    (net (code "57") (name "Net-(FB7-P$1)") (class "Default")
      (node (ref "F24") (pin "1") (pinfunction "1_1") (pintype "passive"))
      (node (ref "FB7") (pin "1") (pinfunction "P$1_1") (pintype "passive"))
    )
    (net (code "58") (name "Net-(FB8-P$1)") (class "Default")
      (node (ref "F23") (pin "1") (pinfunction "1_1") (pintype "passive"))
      (node (ref "FB8") (pin "1") (pinfunction "P$1_1") (pintype "passive"))
    )
    (net (code "59") (name "Net-(FB9-P$1)") (class "Default")
      (node (ref "F22") (pin "1") (pinfunction "1_1") (pintype "passive"))
      (node (ref "FB9") (pin "1") (pinfunction "P$1_1") (pintype "passive"))
    )
    (net (code "60") (name "Net-(FB10-P$1)") (class "Default")
      (node (ref "F21") (pin "1") (pinfunction "1_1") (pintype "passive"))
      (node (ref "FB10") (pin "1") (pinfunction "P$1_1") (pintype "passive"))
    )
    (net (code "61") (name "Net-(LED1-PadA)") (class "Default")
      (node (ref "LED1") (pin "A") (pinfunction "A_A") (pintype "passive"))
      (node (ref "R16") (pin "1") (pinfunction "1_1") (pintype "passive"))
    )
    (net (code "62") (name "Net-(Q2-FO)") (class "Default")
      (node (ref "C8") (pin "2") (pinfunction "2_2") (pintype "passive"))
      (node (ref "Q2") (pin "3") (pinfunction "FO_3") (pintype "output"))
    )
    (net (code "63") (name "Net-(TVS7-VBUS)") (class "Default")
      (node (ref "C20") (pin "2") (pinfunction "2_2") (pintype "passive"))
      (node (ref "TVS7") (pin "5") (pinfunction "VBUS_5") (pintype "bidirectional"))
    )
    (net (code "64") (name "Net-(TVS8-VBUS)") (class "Default")
      (node (ref "C21") (pin "2") (pinfunction "2_2") (pintype "passive"))
      (node (ref "TVS8") (pin "5") (pinfunction "VBUS_5") (pintype "bidirectional"))
    )
    (net (code "65") (name "PROG") (class "Default")
      (node (ref "IC1") (pin "2") (pinfunction "PIO2_0/DTR/SSEL1_2") (pintype "bidirectional"))
      (node (ref "JP8") (pin "1") (pinfunction "1_1") (pintype "passive"))
      (node (ref "LED1") (pin "C") (pinfunction "C_C") (pintype "passive"))
    )
    (net (code "66") (name "RESET") (class "Default")
      (node (ref "C9") (pin "2") (pinfunction "2_2") (pintype "passive"))
      (node (ref "IC1") (pin "3") (pinfunction "RESET/PIO0_0_3") (pintype "bidirectional"))
      (node (ref "R14") (pin "1") (pinfunction "1_1") (pintype "passive"))
      (node (ref "R23") (pin "2") (pinfunction "2_2") (pintype "passive"))
    )
    (net (code "67") (name "SCK1") (class "Default")
      (node (ref "IC1") (pin "43") (pinfunction "PIO3_2/DCD/CT16B0_MAT2/SCK1_43") (pintype "bidirectional"))
      (node (ref "IC2") (pin "6") (pinfunction "SCK_6") (pintype "bidirectional"))
    )
    (net (code "68") (name "SSEL1") (class "Default")
      (node (ref "IC1") (pin "19") (pinfunction "PIO2_4/CT16B1_MAT1/SSEL1_19") (pintype "bidirectional"))
      (node (ref "IC2") (pin "1") (pinfunction "CS_1") (pintype "bidirectional"))
      (node (ref "R1") (pin "1") (pinfunction "1_1") (pintype "passive"))
    )
    (net (code "69") (name "SWCLK") (class "Default")
      (node (ref "IC1") (pin "29") (pinfunction "SWCLK/PIO0_10/SCK0/CT16B0_MAT2_29") (pintype "bidirectional"))
      (node (ref "R17") (pin "1") (pinfunction "1_1") (pintype "passive"))
    )
    (net (code "70") (name "SWDIO") (class "Default")
      (node (ref "IC1") (pin "39") (pinfunction "SWDIO/PIO1_3/AD4/CT32B1_MAT2_39") (pintype "bidirectional"))
      (node (ref "R19") (pin "1") (pinfunction "1_1") (pintype "passive"))
    )
    (net (code "71") (name "unconnected-(IC1-PIO0_2{slash}SSEL0{slash}CT16B0_CAP0-Pad10)") (class "Default")
      (node (ref "IC1") (pin "10") (pinfunction "PIO0_2/SSEL0/CT16B0_CAP0_10") (pintype "bidirectional"))
    )
    (net (code "72") (name "unconnected-(IC1-PIO0_8{slash}MISO0{slash}CT16B0_MAT0-Pad27)") (class "Default")
      (node (ref "IC1") (pin "27") (pinfunction "PIO0_8/MISO0/CT16B0_MAT0_27") (pintype "bidirectional"))
    )
    (net (code "73") (name "unconnected-(IC1-PIO0_9{slash}MOSI0{slash}CT16B0_MAT1-Pad28)") (class "Default")
      (node (ref "IC1") (pin "28") (pinfunction "PIO0_9/MOSI0/CT16B0_MAT1_28") (pintype "bidirectional"))
    )
    (net (code "74") (name "unconnected-(IC1-PIO1_4{slash}AD5{slash}CT32B1_MAT3{slash}WAKEUP-Pad40)") (class "Default")
      (node (ref "IC1") (pin "40") (pinfunction "PIO1_4/AD5/CT32B1_MAT3/WAKEUP_40") (pintype "bidirectional"))
    )
    (net (code "75") (name "unconnected-(IC1-PIO1_5{slash}RTS{slash}CT32B0_CAP0-Pad45)") (class "Default")
      (node (ref "IC1") (pin "45") (pinfunction "PIO1_5/RTS/CT32B0_CAP0_45") (pintype "bidirectional"))
    )
    (net (code "76") (name "unconnected-(IC1-PIO1_10{slash}AD6{slash}CT16B1_MAT1{slash}MISO1-Pad30)") (class "Default")
      (node (ref "IC1") (pin "30") (pinfunction "PIO1_10/AD6/CT16B1_MAT1/MISO1_30") (pintype "bidirectional"))
    )
    (net (code "77") (name "unconnected-(IC1-PIO2_7{slash}CT32B0_MAT2{slash}RXD-Pad11)") (class "Default")
      (node (ref "IC1") (pin "11") (pinfunction "PIO2_7/CT32B0_MAT2/RXD_11") (pintype "bidirectional"))
    )
    (net (code "78") (name "unconnected-(IC1-PIO2_8{slash}CT32B0_MAT3{slash}TXD-Pad12)") (class "Default")
      (node (ref "IC1") (pin "12") (pinfunction "PIO2_8/CT32B0_MAT3/TXD_12") (pintype "bidirectional"))
    )
    (net (code "79") (name "unconnected-(IC1-PIO2_10-Pad25)") (class "Default")
      (node (ref "IC1") (pin "25") (pinfunction "PIO2_10_25") (pintype "bidirectional"))
    )
    (net (code "80") (name "unconnected-(IC1-PIO2_11{slash}SCK0{slash}CT32B0_CAP1-Pad31)") (class "Default")
      (node (ref "IC1") (pin "31") (pinfunction "PIO2_11/SCK0/CT32B0_CAP1_31") (pintype "bidirectional"))
    )
    (net (code "81") (name "unconnected-(IC1-PIO3_3{slash}RI{slash}CT16B0_CAP0-Pad48)") (class "Default")
      (node (ref "IC1") (pin "48") (pinfunction "PIO3_3/RI/CT16B0_CAP0_48") (pintype "bidirectional"))
    )
    (net (code "82") (name "unconnected-(IC1-TDI{slash}PIO0_11{slash}AD0{slash}CT32B0_MAT3-Pad32)") (class "Default")
      (node (ref "IC1") (pin "32") (pinfunction "TDI/PIO0_11/AD0/CT32B0_MAT3_32") (pintype "bidirectional"))
    )
    (net (code "83") (name "unconnected-(IC1-TDO{slash}PIO1_1{slash}AD2{slash}CT32B1_MAT0-Pad34)") (class "Default")
      (node (ref "IC1") (pin "34") (pinfunction "TDO/PIO1_1/AD2/CT32B1_MAT0_34") (pintype "bidirectional"))
    )
    (net (code "84") (name "unconnected-(IC1-TMS{slash}PIO1_0{slash}AD1{slash}CT32B1_CAP0-Pad33)") (class "Default")
      (node (ref "IC1") (pin "33") (pinfunction "TMS/PIO1_0/AD1/CT32B1_CAP0_33") (pintype "bidirectional"))
    )
    (net (code "85") (name "unconnected-(IC1-TRST{slash}PIO1_2{slash}AD3{slash}CT32B1_MAT1-Pad35)") (class "Default")
      (node (ref "IC1") (pin "35") (pinfunction "TRST/PIO1_2/AD3/CT32B1_MAT1_35") (pintype "bidirectional"))
    )
    (net (code "86") (name "unconnected-(IC1-XTALOUT-Pad7)") (class "Default")
      (node (ref "IC1") (pin "7") (pinfunction "XTALOUT_7") (pintype "output"))
    )
    (net (code "87") (name "unconnected-(JP4-Pad1)") (class "Default")
      (node (ref "JP4") (pin "1") (pinfunction "1_1") (pintype "passive"))
    )
    (net (code "88") (name "unconnected-(JP4-Pad2)") (class "Default")
      (node (ref "JP4") (pin "2") (pinfunction "2_2") (pintype "passive"))
    )
    (net (code "89") (name "unconnected-(JP7-Pad6)") (class "Default")
      (node (ref "JP7") (pin "6") (pinfunction "6_6") (pintype "passive"))
    )
    (net (code "90") (name "unconnected-(JP7-Pad8)") (class "Default")
      (node (ref "JP7") (pin "8") (pinfunction "8_8") (pintype "passive"))
    )
  )
)
